# Power.net
KiCad netlist of a schematic drawn in Altium Designer
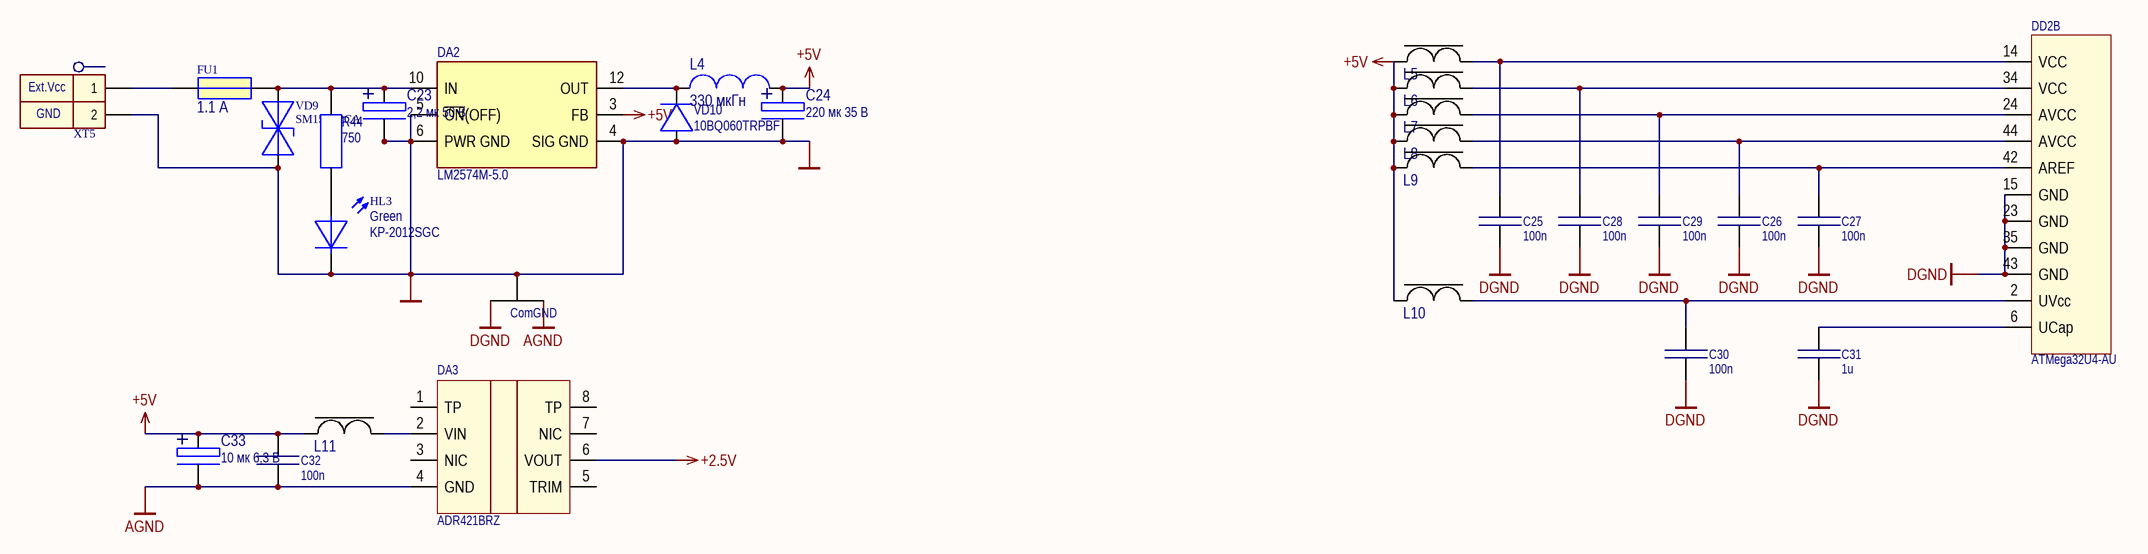
[diagram p0: Power.SchDoc]

(export (version "E")
  (design (tool "Eeschema 10.0.6"))
  (components
    (comp (ref "C23")
      (value "2,2 мк 50 В")
      (footprint "Cap:CAP_POLAR_ELLYTE_B")
      (description "2,2uF 50V Polar capacitor")
      (fields
        (field (name "MANUFACTURERPARTNUMBER") "CA050M2R20REB-0405")
        (field (name "MANUFACTURER") "Yageo")
      )
      (libsource (lib "Cap") (part "02200_050"))
    )
    (comp (ref "C24")
      (value "220 мк 35 В")
      (footprint "Cap:CAP_POLAR_ELLYTE_G")
      (description "220uF 35V Polar capacitor")
      (fields (field (name "MANUFACTURERPARTNUMBER") "CA035M0220REG") (field (name "MANUFACTURER") "Yageo"))
      (libsource (lib "Cap") (part "220000_035"))
    )
    (comp (ref "C25")
      (value "100n")
      (footprint "SMDRC0805")
      (description "Generic capasitor non-polar")
      (fields (field (name "PARTNUMBER") "Capacitor 0805 100n"))
      (libsource (lib "library") (part "Capacitor"))
    )
    (comp (ref "C26")
      (value "100n")
      (footprint "SMDRC0805")
      (description "Generic capasitor non-polar")
      (fields (field (name "PARTNUMBER") "Capacitor 0805 100n"))
      (libsource (lib "library") (part "Capacitor"))
    )
    (comp (ref "C27")
      (value "100n")
      (footprint "SMDRC0805")
      (description "Generic capasitor non-polar")
      (fields (field (name "PARTNUMBER") "Capacitor 0805 100n"))
      (libsource (lib "library") (part "Capacitor"))
    )
    (comp (ref "C28")
      (value "100n")
      (footprint "SMDRC0805")
      (description "Generic capasitor non-polar")
      (fields (field (name "PARTNUMBER") "Capacitor 0805 100n"))
      (libsource (lib "library") (part "Capacitor"))
    )
    (comp (ref "C29")
      (value "100n")
      (footprint "SMDRC0805")
      (description "Generic capasitor non-polar")
      (fields (field (name "PARTNUMBER") "Capacitor 0805 100n"))
      (libsource (lib "library") (part "Capacitor"))
    )
    (comp (ref "C30")
      (value "100n")
      (footprint "SMDRC0805")
      (description "Generic capasitor non-polar")
      (fields (field (name "PARTNUMBER") "Capacitor 0805 100n"))
      (libsource (lib "library") (part "Capacitor"))
    )
    (comp (ref "C31")
      (value "1u")
      (footprint "SMDRC0805")
      (description "Generic capasitor non-polar")
      (fields (field (name "PARTNUMBER") "Capacitor 0805 1u"))
      (libsource (lib "library") (part "Capacitor"))
    )
    (comp (ref "C32")
      (value "100n")
      (footprint "SMDRC0805")
      (description "Generic capasitor non-polar")
      (fields (field (name "PARTNUMBER") "Capacitor 0805 100n"))
      (libsource (lib "library") (part "Capacitor"))
    )
    (comp (ref "C33")
      (value "10 мк 6,3 В")
      (footprint "К50-6")
      (description "10uF 6,3V Polar through-hole cap")
      (fields (field (name "MANUFACTURERPARTNUMBER") "К-50-6"))
      (libsource (lib "Cap") (part "10000_006-К50"))
    )
    (comp (ref "DA2")
      (value "LM2574M-5.0")
      (footprint "Power:SOIC127P1030X264-14M")
      (fields (field (name "MANUFACTURERPARTNUMBER") "LM2574M-5.0"))
      (libsource (lib "Power") (part "LM2574M-5.0"))
    )
    (comp (ref "DA3")
      (value "ADR421BRZ")
      (footprint "Power:SO8")
      (description "IC VREF SERIES 2.5V 8SOIC")
      (fields
        (field (name "MANUFACTURER") "Analog Devices Inc.")
        (field (name "MANUFACTURER PART NUMBER") "ADR421ARZ")
      )
      (libsource (lib "Power") (part "ADR421BRZ"))
    )
    (comp (ref "DD2")
      (value "ATMega32U4-AU")
      (footprint "Atmel Microcontroller 8-Bit Automotive AVR:44ML_L")
      (libsource (lib "Microcontrollers") (part "ATMega32U4"))
    )
    (comp (ref "FU1")
      (value "1.1 А")
      (footprint "Power:EFuse 1.1A")
      (description "Fuse")
      (fields (field (name "MANUFACTURERPARTNUMBER") "EFuse LP60-110F"))
      (libsource (lib "Power") (part "EFuse LP60-110F"))
    )
    (comp (ref "GND1")
      (value "ComGND")
      (footprint "IntLib:ComGND")
      (libsource (lib "IntLib") (part "ComGND"))
    )
    (comp (ref "HL3")
      (value "Green")
      (footprint "Indicator:DIOMELF2012M")
      (description "Diod LED SMD Green")
      (fields (field (name "MANUFACTURERPARTNUMBER") "KP-2012SGC"))
      (libsource (lib "Indicator") (part "LED1_G"))
    )
    (comp (ref "L4")
      (value "330 мкГн")
      (footprint "Inductor:INDP7972X50M")
      (description "Inductor")
      (fields (field (name "MANUFACTURERPARTNUMBER") "SCD0705T-331K-N"))
      (libsource (lib "Inductor") (part "SCD0705T-331K-N"))
    )
    (comp (ref "L5")
      (value "MPZ1608S181A")
      (footprint "Inductor:INDC0603X03M")
      (description "Ferrite Bead")
      (libsource (lib "Inductor") (part "Ferrite Bead"))
    )
    (comp (ref "L6")
      (value "MPZ1608S181A")
      (footprint "Inductor:INDC0603X03M")
      (description "Ferrite Bead")
      (libsource (lib "Inductor") (part "Ferrite Bead"))
    )
    (comp (ref "L7")
      (value "MPZ1608S181A")
      (footprint "Inductor:INDC0603X03M")
      (description "Ferrite Bead")
      (libsource (lib "Inductor") (part "Ferrite Bead"))
    )
    (comp (ref "L8")
      (value "MPZ1608S181A")
      (footprint "Inductor:INDC0603X03M")
      (description "Ferrite Bead")
      (libsource (lib "Inductor") (part "Ferrite Bead"))
    )
    (comp (ref "L9")
      (value "MPZ1608S181A")
      (footprint "Inductor:INDC0603X03M")
      (description "Ferrite Bead")
      (libsource (lib "Inductor") (part "Ferrite Bead"))
    )
    (comp (ref "L10")
      (value "MPZ1608S181A")
      (footprint "Inductor:INDC0603X03M")
      (description "Ferrite Bead")
      (libsource (lib "Inductor") (part "Ferrite Bead"))
    )
    (comp (ref "L11")
      (value "MPZ1608S181A")
      (footprint "Inductor:INDC0603X03M")
      (description "Ferrite Bead")
      (libsource (lib "") (part "Ferrite Bead_1"))
    )
    (comp (ref "R44")
      (value "750")
      (footprint "SMDRC0805")
      (description "Generic resistor")
      (fields (field (name "PARTNUMBER") "Resistor 0805 750"))
      (libsource (lib "library") (part "Resistor"))
    )
    (comp (ref "VD9")
      (value "SM15T12CA")
      (footprint "DIod:SUPRES3216X18N")
      (description "Diod suppressor")
      (fields
        (field (name "MANUFACTURER") "ST Microelectronics")
        (field (name "MANUFACTURERPARTNUMBER") "SM15T12CA")
      )
      (libsource (lib "Diod") (part "SM15T12CA"))
    )
    (comp (ref "VD10")
      (value "10BQ060TRPBF")
      (footprint "DIod:SHOTKY 4.1x3.3")
      (description "DIODE SCHOTTKY 60V 1A DO214AA")
      (fields
        (field (name "MANUFACTURER") "Vishay Semiconductor Diodes Division")
        (field (name "MANUFACTURERPARTNUMBER") "10BQ060TRPBF")
      )
      (libsource (lib "Diod") (part "10BQ060TRPBF"))
    )
    (comp (ref "XT5")
      (value "330-021-12")
      (footprint "Connector:330-021-12")
      (description "Demountable connection  2-pin")
      (fields (field (name "MANUFACTURER") "Degson Electronics Co., Ltd"))
      (libsource (lib "Connector") (part "Con2_D 330-021-12"))
    )
  )
  (nets
    (net (code "1") (name "+2.5V") (class "Default")
      (node (ref "DA3") (pin "6") (pinfunction "VOUT_6") (pintype "passive"))
    )
    (net (code "2") (name "+5V") (class "Default")
      (node (ref "C24") (pin "2") (pinfunction "+_2") (pintype "passive"))
      (node (ref "C32") (pin "2") (pintype "passive"))
      (node (ref "C33") (pin "2") (pinfunction "+_2") (pintype "passive"))
      (node (ref "DA2") (pin "3") (pinfunction "FB_3") (pintype "passive"))
      (node (ref "L10") (pin "1") (pinfunction "1_1") (pintype "passive"))
      (node (ref "L11") (pin "2") (pinfunction "2_2") (pintype "passive"))
      (node (ref "L4") (pin "1") (pinfunction "1_1") (pintype "passive"))
      (node (ref "L5") (pin "1") (pinfunction "1_1") (pintype "passive"))
      (node (ref "L6") (pin "1") (pinfunction "1_1") (pintype "passive"))
      (node (ref "L7") (pin "1") (pinfunction "1_1") (pintype "passive"))
      (node (ref "L8") (pin "1") (pinfunction "1_1") (pintype "passive"))
      (node (ref "L9") (pin "1") (pinfunction "1_1") (pintype "passive"))
    )
    (net (code "3") (name "AGND") (class "Default")
      (node (ref "C32") (pin "1") (pintype "passive"))
      (node (ref "C33") (pin "1") (pinfunction "-_1") (pintype "passive"))
      (node (ref "DA3") (pin "4") (pinfunction "GND_4") (pintype "passive"))
      (node (ref "GND1") (pin "1") (pinfunction "1_1") (pintype "passive"))
    )
    (net (code "4") (name "DGND") (class "Default")
      (node (ref "C25") (pin "2") (pintype "passive"))
      (node (ref "C26") (pin "2") (pintype "passive"))
      (node (ref "C27") (pin "2") (pintype "passive"))
      (node (ref "C28") (pin "2") (pintype "passive"))
      (node (ref "C29") (pin "2") (pintype "passive"))
      (node (ref "C30") (pin "2") (pintype "passive"))
      (node (ref "C31") (pin "2") (pintype "passive"))
      (node (ref "DD2") (pin "15") (pinfunction "GND_15") (pintype "power_in"))
      (node (ref "DD2") (pin "23") (pinfunction "GND_23") (pintype "power_in"))
      (node (ref "DD2") (pin "35") (pinfunction "GND_35") (pintype "power_in"))
      (node (ref "DD2") (pin "43") (pinfunction "GND_43") (pintype "power_in"))
      (node (ref "GND1") (pin "3") (pinfunction "3_3") (pintype "passive"))
    )
    (net (code "5") (name "GND") (class "Default")
      (node (ref "C23") (pin "1") (pinfunction "-_1") (pintype "passive"))
      (node (ref "C24") (pin "1") (pinfunction "-_1") (pintype "passive"))
      (node (ref "DA2") (pin "4") (pinfunction "SIG_GND_4") (pintype "passive"))
      (node (ref "DA2") (pin "5") (pinfunction "~{ON}(OFF)_5") (pintype "passive"))
      (node (ref "DA2") (pin "6") (pinfunction "PWR_GND_6") (pintype "passive"))
      (node (ref "GND1") (pin "2") (pinfunction "2_2") (pintype "passive"))
      (node (ref "HL3") (pin "2") (pinfunction "2_2") (pintype "passive"))
      (node (ref "VD10") (pin "A") (pinfunction "A_A") (pintype "passive"))
      (node (ref "VD9") (pin "1") (pinfunction "1_1") (pintype "passive"))
      (node (ref "XT5") (pin "2") (pinfunction "2_2") (pintype "passive"))
    )
    (net (code "6") (name "Net-(C23-+)") (class "Default")
      (node (ref "C23") (pin "2") (pinfunction "+_2") (pintype "passive"))
      (node (ref "DA2") (pin "10") (pinfunction "IN_10") (pintype "passive"))
      (node (ref "FU1") (pin "2") (pinfunction "2_2") (pintype "passive"))
      (node (ref "R44") (pin "2") (pinfunction "2_2") (pintype "passive"))
      (node (ref "VD9") (pin "2") (pinfunction "2_2") (pintype "passive"))
    )
    (net (code "7") (name "Net-(C25-Pad1)") (class "Default")
      (node (ref "C25") (pin "1") (pintype "passive"))
      (node (ref "DD2") (pin "14") (pinfunction "VCC_14") (pintype "power_in"))
      (node (ref "L5") (pin "2") (pinfunction "2_2") (pintype "passive"))
    )
    (net (code "8") (name "Net-(C26-Pad1)") (class "Default")
      (node (ref "C26") (pin "1") (pintype "passive"))
      (node (ref "DD2") (pin "44") (pinfunction "AVCC_44") (pintype "power_in"))
      (node (ref "L8") (pin "2") (pinfunction "2_2") (pintype "passive"))
    )
    (net (code "9") (name "Net-(C28-Pad1)") (class "Default")
      (node (ref "C28") (pin "1") (pintype "passive"))
      (node (ref "DD2") (pin "34") (pinfunction "VCC_34") (pintype "power_in"))
      (node (ref "L6") (pin "2") (pinfunction "2_2") (pintype "passive"))
    )
    (net (code "10") (name "Net-(C29-Pad1)") (class "Default")
      (node (ref "C29") (pin "1") (pintype "passive"))
      (node (ref "DD2") (pin "24") (pinfunction "AVCC_24") (pintype "power_in"))
      (node (ref "L7") (pin "2") (pinfunction "2_2") (pintype "passive"))
    )
    (net (code "11") (name "Net-(DA2-OUT)") (class "Default")
      (node (ref "DA2") (pin "12") (pinfunction "OUT_12") (pintype "passive"))
      (node (ref "L4") (pin "2") (pinfunction "2_2") (pintype "passive"))
      (node (ref "VD10") (pin "K") (pinfunction "K_K") (pintype "passive"))
    )
    (net (code "12") (name "Net-(DA3-VIN)") (class "Default")
      (node (ref "DA3") (pin "2") (pinfunction "VIN_2") (pintype "passive"))
      (node (ref "L11") (pin "1") (pinfunction "1_1") (pintype "passive"))
    )
    (net (code "13") (name "Net-(DD2B-AREF)") (class "Default")
      (node (ref "C27") (pin "1") (pintype "passive"))
      (node (ref "DD2") (pin "42") (pinfunction "AREF_42") (pintype "power_in"))
      (node (ref "L9") (pin "2") (pinfunction "2_2") (pintype "passive"))
    )
    (net (code "14") (name "Net-(DD2B-UCap)") (class "Default")
      (node (ref "C31") (pin "1") (pintype "passive"))
      (node (ref "DD2") (pin "6") (pinfunction "UCap_6") (pintype "passive"))
    )
    (net (code "15") (name "Net-(DD2B-UVcc)") (class "Default")
      (node (ref "C30") (pin "1") (pintype "passive"))
      (node (ref "DD2") (pin "2") (pinfunction "UVcc_2") (pintype "power_in"))
      (node (ref "L10") (pin "2") (pinfunction "2_2") (pintype "passive"))
    )
    (net (code "16") (name "Net-(FU1-Pad1)") (class "Default")
      (node (ref "FU1") (pin "1") (pinfunction "1_1") (pintype "passive"))
      (node (ref "XT5") (pin "1") (pinfunction "1_1") (pintype "passive"))
    )
    (net (code "17") (name "Net-(HL3-Pad1)") (class "Default")
      (node (ref "HL3") (pin "1") (pinfunction "1_1") (pintype "passive"))
      (node (ref "R44") (pin "1") (pinfunction "1_1") (pintype "passive"))
    )
    (net (code "18") (name "unconnected-(DA3-NIC-Pad3)") (class "Default")
      (node (ref "DA3") (pin "3") (pinfunction "NIC_3") (pintype "passive"))
    )
    (net (code "19") (name "unconnected-(DA3-NIC-Pad7)") (class "Default")
      (node (ref "DA3") (pin "7") (pinfunction "NIC_7") (pintype "passive"))
    )
    (net (code "20") (name "unconnected-(DA3-TP-Pad1)") (class "Default")
      (node (ref "DA3") (pin "1") (pinfunction "TP_1") (pintype "passive"))
    )
    (net (code "21") (name "unconnected-(DA3-TP-Pad8)") (class "Default")
      (node (ref "DA3") (pin "8") (pinfunction "TP_8") (pintype "passive"))
    )
    (net (code "22") (name "unconnected-(DA3-TRIM-Pad5)") (class "Default")
      (node (ref "DA3") (pin "5") (pinfunction "TRIM_5") (pintype "passive"))
    )
  )
)
